# digital_clock_run4.net
KiCad netlist of a schematic drawn in EasyEDA
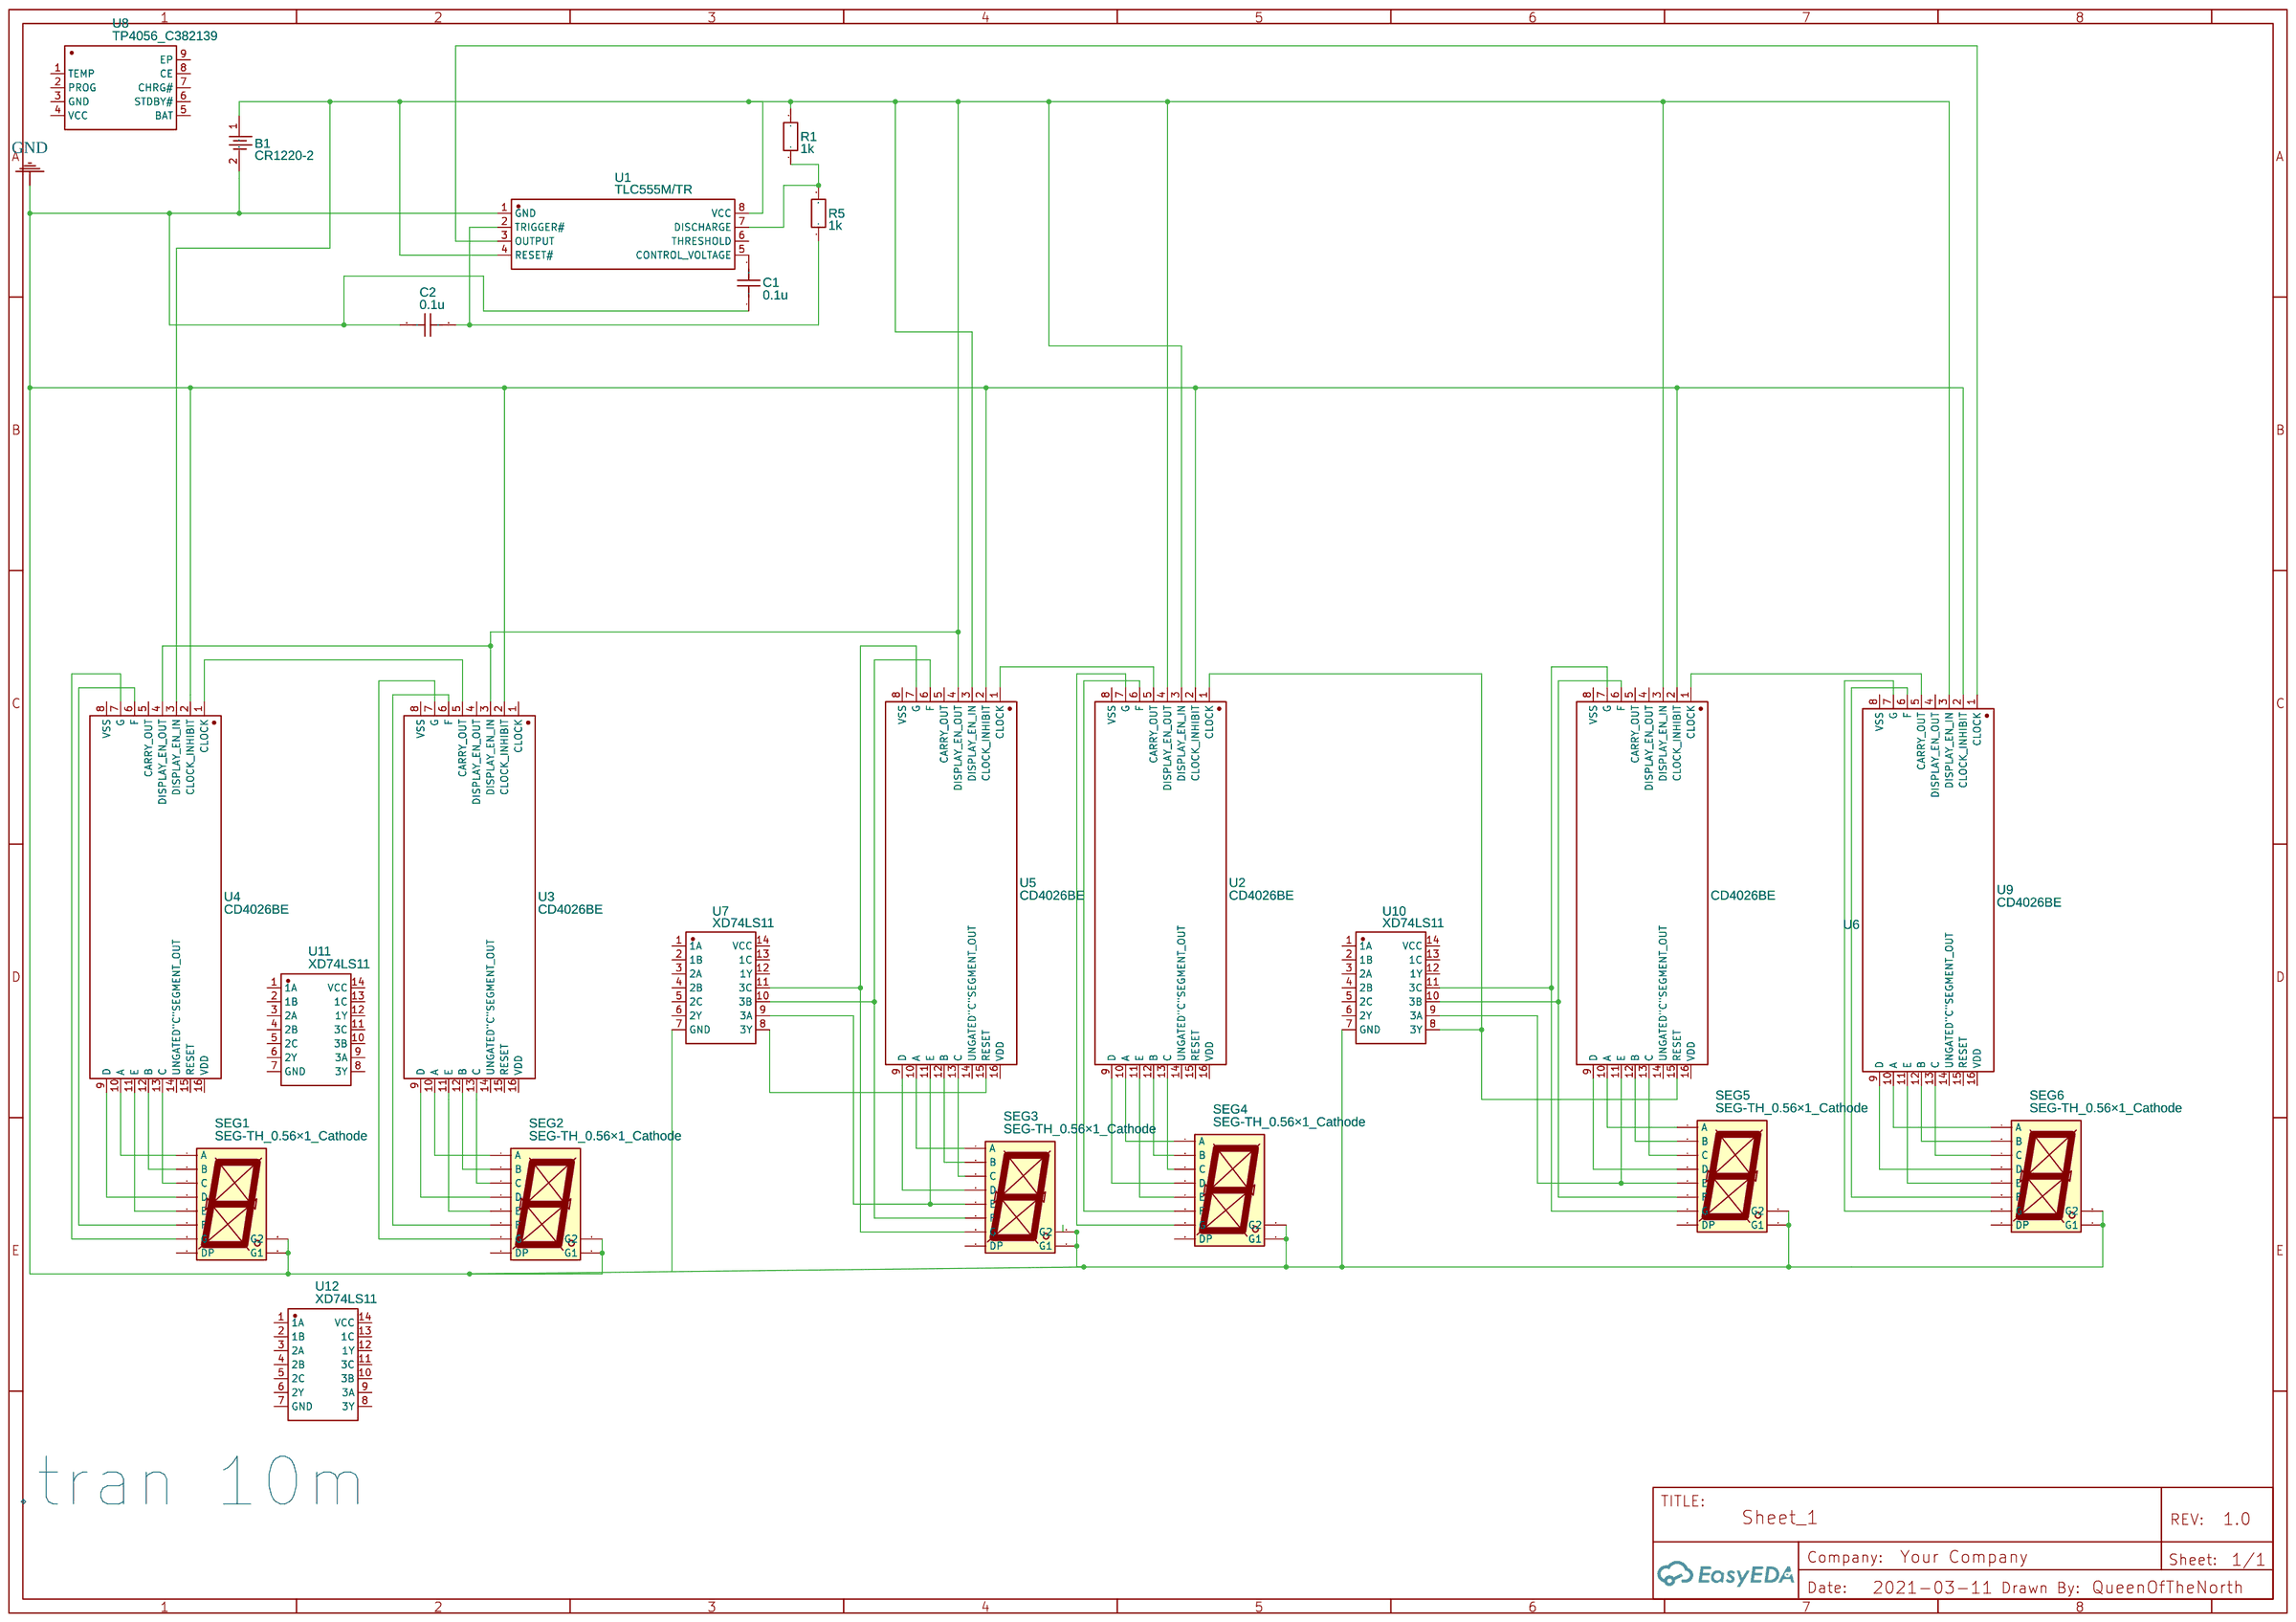
[diagram p0: schematic sheet]

(export (version "E")
  (design (tool "Eeschema 10.0.6"))
  (components
    (comp (ref "B1")
      (value "CR1220-2")
      (fields (field (name "BOM_Supplier Part") "C70381"))
      (libsource (lib "") (part "CR1220-2"))
    )
    (comp (ref "C1") (value "0.1u") (libsource (lib "") (part "C_0603_US")))
    (comp (ref "C2") (value "0.1u") (libsource (lib "") (part "C_0603_US_1")))
    (comp (ref "R1") (value "1k") (libsource (lib "") (part "R_0603_EU")))
    (comp (ref "R5") (value "1k") (libsource (lib "") (part "R_0603_EU")))
    (comp (ref "SEG1")
      (value "SEG-TH_0.56×1_Cathode")
      (fields (field (name "BOM_Supplier Part") "C8093"))
      (libsource (lib "") (part "SEG-TH_0.56×1_Cathode"))
    )
    (comp (ref "SEG2")
      (value "SEG-TH_0.56×1_Cathode")
      (fields (field (name "BOM_Supplier Part") "C8093"))
      (libsource (lib "") (part "SEG-TH_0.56×1_Cathode"))
    )
    (comp (ref "SEG3")
      (value "SEG-TH_0.56×1_Cathode")
      (fields (field (name "BOM_Supplier Part") "C8093"))
      (libsource (lib "") (part "SEG-TH_0.56×1_Cathode"))
    )
    (comp (ref "SEG4")
      (value "SEG-TH_0.56×1_Cathode")
      (fields (field (name "BOM_Supplier Part") "C8093"))
      (libsource (lib "") (part "SEG-TH_0.56×1_Cathode"))
    )
    (comp (ref "SEG5")
      (value "SEG-TH_0.56×1_Cathode")
      (fields (field (name "BOM_Supplier Part") "C8093"))
      (libsource (lib "") (part "SEG-TH_0.56×1_Cathode"))
    )
    (comp (ref "SEG6")
      (value "SEG-TH_0.56×1_Cathode")
      (fields (field (name "BOM_Supplier Part") "C8093"))
      (libsource (lib "") (part "SEG-TH_0.56×1_Cathode"))
    )
    (comp (ref "U1")
      (value "TLC555M/TR")
      (fields (field (name "BOM_Supplier Part") "C383061"))
      (libsource (lib "") (part "TLC555M/TR"))
    )
    (comp (ref "U2")
      (value "CD4026BE")
      (fields (field (name "BOM_Supplier Part") "C89909"))
      (libsource (lib "") (part "CD4026BE"))
    )
    (comp (ref "U3")
      (value "CD4026BE")
      (fields (field (name "BOM_Supplier Part") "C89909"))
      (libsource (lib "") (part "CD4026BE"))
    )
    (comp (ref "U4")
      (value "CD4026BE")
      (fields (field (name "BOM_Supplier Part") "C89909"))
      (libsource (lib "") (part "CD4026BE"))
    )
    (comp (ref "U5")
      (value "CD4026BE")
      (fields (field (name "BOM_Supplier Part") "C89909"))
      (libsource (lib "") (part "CD4026BE"))
    )
    (comp (ref "U6")
      (value "CD4026BE")
      (fields (field (name "BOM_Supplier Part") "C89909"))
      (libsource (lib "") (part "CD4026BE"))
    )
    (comp (ref "U7")
      (value "XD74LS11")
      (fields (field (name "BOM_Supplier Part") "C521167"))
      (libsource (lib "") (part "XD74LS11"))
    )
    (comp (ref "U8")
      (value "TP4056_C382139")
      (fields (field (name "BOM_Manufacturer Part") "TP4056") (field (name "BOM_Supplier Part") "C382139"))
      (libsource (lib "") (part "TP4056_C382139"))
    )
    (comp (ref "U9")
      (value "CD4026BE")
      (fields (field (name "BOM_Supplier Part") "C89909"))
      (libsource (lib "") (part "CD4026BE"))
    )
    (comp (ref "U10")
      (value "XD74LS11")
      (fields (field (name "BOM_Supplier Part") "C521167"))
      (libsource (lib "") (part "XD74LS11"))
    )
    (comp (ref "U11")
      (value "XD74LS11")
      (fields (field (name "BOM_Supplier Part") "C521167"))
      (libsource (lib "") (part "XD74LS11"))
    )
    (comp (ref "U12")
      (value "XD74LS11")
      (fields (field (name "BOM_Supplier Part") "C521167"))
      (libsource (lib "") (part "XD74LS11"))
    )
  )
  (nets
    (net (code "1") (name "GND") (class "Default")
      (node (ref "B1") (pin "2") (pinfunction "2_2") (pintype "input"))
      (node (ref "C1") (pin "1") (pinfunction "1_1") (pintype "unspecified"))
      (node (ref "C2") (pin "1") (pinfunction "1_1") (pintype "unspecified"))
      (node (ref "SEG1") (pin "3") (pinfunction "G1_3") (pintype "unspecified"))
      (node (ref "SEG1") (pin "8") (pinfunction "G2_8") (pintype "unspecified"))
      (node (ref "SEG2") (pin "3") (pinfunction "G1_3") (pintype "unspecified"))
      (node (ref "SEG2") (pin "8") (pinfunction "G2_8") (pintype "unspecified"))
      (node (ref "SEG3") (pin "3") (pinfunction "G1_3") (pintype "unspecified"))
      (node (ref "SEG3") (pin "8") (pinfunction "G2_8") (pintype "unspecified"))
      (node (ref "SEG4") (pin "3") (pinfunction "G1_3") (pintype "unspecified"))
      (node (ref "SEG4") (pin "8") (pinfunction "G2_8") (pintype "unspecified"))
      (node (ref "SEG5") (pin "3") (pinfunction "G1_3") (pintype "unspecified"))
      (node (ref "SEG5") (pin "8") (pinfunction "G2_8") (pintype "unspecified"))
      (node (ref "SEG6") (pin "3") (pinfunction "G1_3") (pintype "unspecified"))
      (node (ref "SEG6") (pin "8") (pinfunction "G2_8") (pintype "unspecified"))
      (node (ref "U1") (pin "1") (pinfunction "GND_1") (pintype "unspecified"))
      (node (ref "U10") (pin "7") (pinfunction "GND_7") (pintype "unspecified"))
      (node (ref "U2") (pin "2") (pinfunction "CLOCK_INHIBIT_2") (pintype "unspecified"))
      (node (ref "U3") (pin "2") (pinfunction "CLOCK_INHIBIT_2") (pintype "unspecified"))
      (node (ref "U4") (pin "2") (pinfunction "CLOCK_INHIBIT_2") (pintype "unspecified"))
      (node (ref "U5") (pin "2") (pinfunction "CLOCK_INHIBIT_2") (pintype "unspecified"))
      (node (ref "U6") (pin "2") (pinfunction "CLOCK_INHIBIT_2") (pintype "unspecified"))
      (node (ref "U9") (pin "2") (pinfunction "CLOCK_INHIBIT_2") (pintype "unspecified"))
    )
    (net (code "2") (name "Net-(SEG1-A)") (class "Default")
      (node (ref "SEG1") (pin "7") (pinfunction "A_7") (pintype "unspecified"))
      (node (ref "U4") (pin "10") (pinfunction "A_10") (pintype "unspecified"))
    )
    (net (code "3") (name "Net-(SEG1-B)") (class "Default")
      (node (ref "SEG1") (pin "6") (pinfunction "B_6") (pintype "unspecified"))
      (node (ref "U4") (pin "12") (pinfunction "B_12") (pintype "unspecified"))
    )
    (net (code "4") (name "Net-(SEG1-C)") (class "Default")
      (node (ref "SEG1") (pin "4") (pinfunction "C_4") (pintype "unspecified"))
      (node (ref "U4") (pin "13") (pinfunction "C_13") (pintype "unspecified"))
    )
    (net (code "5") (name "Net-(SEG1-D)") (class "Default")
      (node (ref "SEG1") (pin "2") (pinfunction "D_2") (pintype "unspecified"))
      (node (ref "U4") (pin "9") (pinfunction "D_9") (pintype "unspecified"))
    )
    (net (code "6") (name "Net-(SEG1-E)") (class "Default")
      (node (ref "SEG1") (pin "1") (pinfunction "E_1") (pintype "unspecified"))
      (node (ref "U4") (pin "11") (pinfunction "E_11") (pintype "unspecified"))
    )
    (net (code "7") (name "Net-(SEG1-F)") (class "Default")
      (node (ref "SEG1") (pin "9") (pinfunction "F_9") (pintype "unspecified"))
      (node (ref "U4") (pin "6") (pinfunction "F_6") (pintype "unspecified"))
    )
    (net (code "8") (name "Net-(SEG1-G)") (class "Default")
      (node (ref "SEG1") (pin "10") (pinfunction "G_10") (pintype "unspecified"))
      (node (ref "U4") (pin "7") (pinfunction "G_7") (pintype "unspecified"))
    )
    (net (code "9") (name "Net-(SEG2-A)") (class "Default")
      (node (ref "SEG2") (pin "7") (pinfunction "A_7") (pintype "unspecified"))
      (node (ref "U3") (pin "10") (pinfunction "A_10") (pintype "unspecified"))
    )
    (net (code "10") (name "Net-(SEG2-B)") (class "Default")
      (node (ref "SEG2") (pin "6") (pinfunction "B_6") (pintype "unspecified"))
      (node (ref "U3") (pin "12") (pinfunction "B_12") (pintype "unspecified"))
    )
    (net (code "11") (name "Net-(SEG2-C)") (class "Default")
      (node (ref "SEG2") (pin "4") (pinfunction "C_4") (pintype "unspecified"))
      (node (ref "U3") (pin "13") (pinfunction "C_13") (pintype "unspecified"))
    )
    (net (code "12") (name "Net-(SEG2-D)") (class "Default")
      (node (ref "SEG2") (pin "2") (pinfunction "D_2") (pintype "unspecified"))
      (node (ref "U3") (pin "9") (pinfunction "D_9") (pintype "unspecified"))
    )
    (net (code "13") (name "Net-(SEG2-E)") (class "Default")
      (node (ref "SEG2") (pin "1") (pinfunction "E_1") (pintype "unspecified"))
      (node (ref "U3") (pin "11") (pinfunction "E_11") (pintype "unspecified"))
    )
    (net (code "14") (name "Net-(SEG2-F)") (class "Default")
      (node (ref "SEG2") (pin "9") (pinfunction "F_9") (pintype "unspecified"))
      (node (ref "U3") (pin "6") (pinfunction "F_6") (pintype "unspecified"))
    )
    (net (code "15") (name "Net-(SEG2-G)") (class "Default")
      (node (ref "SEG2") (pin "10") (pinfunction "G_10") (pintype "unspecified"))
      (node (ref "U3") (pin "7") (pinfunction "G_7") (pintype "unspecified"))
    )
    (net (code "16") (name "Net-(SEG3-A)") (class "Default")
      (node (ref "SEG3") (pin "7") (pinfunction "A_7") (pintype "unspecified"))
      (node (ref "U5") (pin "10") (pinfunction "A_10") (pintype "unspecified"))
    )
    (net (code "17") (name "Net-(SEG3-B)") (class "Default")
      (node (ref "SEG3") (pin "6") (pinfunction "B_6") (pintype "unspecified"))
      (node (ref "U5") (pin "12") (pinfunction "B_12") (pintype "unspecified"))
    )
    (net (code "18") (name "Net-(SEG3-C)") (class "Default")
      (node (ref "SEG3") (pin "4") (pinfunction "C_4") (pintype "unspecified"))
      (node (ref "U5") (pin "13") (pinfunction "C_13") (pintype "unspecified"))
    )
    (net (code "19") (name "Net-(SEG3-D)") (class "Default")
      (node (ref "SEG3") (pin "2") (pinfunction "D_2") (pintype "unspecified"))
      (node (ref "U5") (pin "9") (pinfunction "D_9") (pintype "unspecified"))
    )
    (net (code "20") (name "Net-(SEG3-E)") (class "Default")
      (node (ref "SEG3") (pin "1") (pinfunction "E_1") (pintype "unspecified"))
      (node (ref "U5") (pin "11") (pinfunction "E_11") (pintype "unspecified"))
      (node (ref "U7") (pin "9") (pinfunction "3A_9") (pintype "unspecified"))
    )
    (net (code "21") (name "Net-(SEG3-F)") (class "Default")
      (node (ref "SEG3") (pin "9") (pinfunction "F_9") (pintype "unspecified"))
      (node (ref "U5") (pin "6") (pinfunction "F_6") (pintype "unspecified"))
      (node (ref "U7") (pin "10") (pinfunction "3B_10") (pintype "unspecified"))
    )
    (net (code "22") (name "Net-(SEG3-G)") (class "Default")
      (node (ref "SEG3") (pin "10") (pinfunction "G_10") (pintype "unspecified"))
      (node (ref "U5") (pin "7") (pinfunction "G_7") (pintype "unspecified"))
      (node (ref "U7") (pin "11") (pinfunction "3C_11") (pintype "unspecified"))
    )
    (net (code "23") (name "Net-(SEG4-A)") (class "Default")
      (node (ref "SEG4") (pin "7") (pinfunction "A_7") (pintype "unspecified"))
      (node (ref "U2") (pin "10") (pinfunction "A_10") (pintype "unspecified"))
    )
    (net (code "24") (name "Net-(SEG4-B)") (class "Default")
      (node (ref "SEG4") (pin "6") (pinfunction "B_6") (pintype "unspecified"))
      (node (ref "U2") (pin "12") (pinfunction "B_12") (pintype "unspecified"))
    )
    (net (code "25") (name "Net-(SEG4-C)") (class "Default")
      (node (ref "SEG4") (pin "4") (pinfunction "C_4") (pintype "unspecified"))
      (node (ref "U2") (pin "13") (pinfunction "C_13") (pintype "unspecified"))
    )
    (net (code "26") (name "Net-(SEG4-D)") (class "Default")
      (node (ref "SEG4") (pin "2") (pinfunction "D_2") (pintype "unspecified"))
      (node (ref "U2") (pin "9") (pinfunction "D_9") (pintype "unspecified"))
    )
    (net (code "27") (name "Net-(SEG4-E)") (class "Default")
      (node (ref "SEG4") (pin "1") (pinfunction "E_1") (pintype "unspecified"))
      (node (ref "U2") (pin "11") (pinfunction "E_11") (pintype "unspecified"))
    )
    (net (code "28") (name "Net-(SEG4-F)") (class "Default")
      (node (ref "SEG4") (pin "9") (pinfunction "F_9") (pintype "unspecified"))
      (node (ref "U2") (pin "6") (pinfunction "F_6") (pintype "unspecified"))
    )
    (net (code "29") (name "Net-(SEG4-G)") (class "Default")
      (node (ref "SEG4") (pin "10") (pinfunction "G_10") (pintype "unspecified"))
      (node (ref "U2") (pin "7") (pinfunction "G_7") (pintype "unspecified"))
    )
    (net (code "30") (name "Net-(SEG5-A)") (class "Default")
      (node (ref "SEG5") (pin "7") (pinfunction "A_7") (pintype "unspecified"))
      (node (ref "U6") (pin "10") (pinfunction "A_10") (pintype "unspecified"))
    )
    (net (code "31") (name "Net-(SEG5-B)") (class "Default")
      (node (ref "SEG5") (pin "6") (pinfunction "B_6") (pintype "unspecified"))
      (node (ref "U6") (pin "12") (pinfunction "B_12") (pintype "unspecified"))
    )
    (net (code "32") (name "Net-(SEG5-C)") (class "Default")
      (node (ref "SEG5") (pin "4") (pinfunction "C_4") (pintype "unspecified"))
      (node (ref "U6") (pin "13") (pinfunction "C_13") (pintype "unspecified"))
    )
    (net (code "33") (name "Net-(SEG5-D)") (class "Default")
      (node (ref "SEG5") (pin "2") (pinfunction "D_2") (pintype "unspecified"))
      (node (ref "U6") (pin "9") (pinfunction "D_9") (pintype "unspecified"))
    )
    (net (code "34") (name "Net-(SEG5-E)") (class "Default")
      (node (ref "SEG5") (pin "1") (pinfunction "E_1") (pintype "unspecified"))
      (node (ref "U10") (pin "9") (pinfunction "3A_9") (pintype "unspecified"))
      (node (ref "U6") (pin "11") (pinfunction "E_11") (pintype "unspecified"))
    )
    (net (code "35") (name "Net-(SEG5-F)") (class "Default")
      (node (ref "SEG5") (pin "9") (pinfunction "F_9") (pintype "unspecified"))
      (node (ref "U10") (pin "10") (pinfunction "3B_10") (pintype "unspecified"))
      (node (ref "U6") (pin "6") (pinfunction "F_6") (pintype "unspecified"))
    )
    (net (code "36") (name "Net-(SEG5-G)") (class "Default")
      (node (ref "SEG5") (pin "10") (pinfunction "G_10") (pintype "unspecified"))
      (node (ref "U10") (pin "11") (pinfunction "3C_11") (pintype "unspecified"))
      (node (ref "U6") (pin "7") (pinfunction "G_7") (pintype "unspecified"))
    )
    (net (code "37") (name "Net-(SEG6-A)") (class "Default")
      (node (ref "SEG6") (pin "7") (pinfunction "A_7") (pintype "unspecified"))
      (node (ref "U9") (pin "10") (pinfunction "A_10") (pintype "unspecified"))
    )
    (net (code "38") (name "Net-(SEG6-B)") (class "Default")
      (node (ref "SEG6") (pin "6") (pinfunction "B_6") (pintype "unspecified"))
      (node (ref "U9") (pin "12") (pinfunction "B_12") (pintype "unspecified"))
    )
    (net (code "39") (name "Net-(SEG6-C)") (class "Default")
      (node (ref "SEG6") (pin "4") (pinfunction "C_4") (pintype "unspecified"))
      (node (ref "U9") (pin "13") (pinfunction "C_13") (pintype "unspecified"))
    )
    (net (code "40") (name "Net-(SEG6-D)") (class "Default")
      (node (ref "SEG6") (pin "2") (pinfunction "D_2") (pintype "unspecified"))
      (node (ref "U9") (pin "9") (pinfunction "D_9") (pintype "unspecified"))
    )
    (net (code "41") (name "Net-(SEG6-E)") (class "Default")
      (node (ref "SEG6") (pin "1") (pinfunction "E_1") (pintype "unspecified"))
      (node (ref "U9") (pin "11") (pinfunction "E_11") (pintype "unspecified"))
    )
    (net (code "42") (name "Net-(SEG6-F)") (class "Default")
      (node (ref "SEG6") (pin "9") (pinfunction "F_9") (pintype "unspecified"))
      (node (ref "U9") (pin "6") (pinfunction "F_6") (pintype "unspecified"))
    )
    (net (code "43") (name "Net-(SEG6-G)") (class "Default")
      (node (ref "SEG6") (pin "10") (pinfunction "G_10") (pintype "unspecified"))
      (node (ref "U9") (pin "7") (pinfunction "G_7") (pintype "unspecified"))
    )
    (net (code "44") (name "Net-(U1-CONTROL_VOLTAGE)") (class "Default")
      (node (ref "C1") (pin "2") (pinfunction "2_2") (pintype "unspecified"))
      (node (ref "U1") (pin "5") (pinfunction "CONTROL_VOLTAGE_5") (pintype "unspecified"))
    )
    (net (code "45") (name "Net-(U1-DISCHARGE)") (class "Default")
      (node (ref "R1") (pin "1") (pinfunction "1_1") (pintype "unspecified"))
      (node (ref "R5") (pin "2") (pinfunction "2_2") (pintype "unspecified"))
      (node (ref "U1") (pin "7") (pinfunction "DISCHARGE_7") (pintype "unspecified"))
    )
    (net (code "46") (name "Net-(U1-OUTPUT)") (class "Default")
      (node (ref "U1") (pin "3") (pinfunction "OUTPUT_3") (pintype "unspecified"))
      (node (ref "U9") (pin "1") (pinfunction "CLOCK_1") (pintype "unspecified"))
    )
    (net (code "47") (name "Net-(U1-RESET#)") (class "Default")
      (node (ref "B1") (pin "1") (pinfunction "1_1") (pintype "input"))
      (node (ref "R1") (pin "2") (pinfunction "2_2") (pintype "unspecified"))
      (node (ref "U1") (pin "4") (pinfunction "RESET#_4") (pintype "unspecified"))
      (node (ref "U1") (pin "8") (pinfunction "VCC_8") (pintype "unspecified"))
      (node (ref "U2") (pin "3") (pinfunction "DISPLAY_EN_IN_3") (pintype "unspecified"))
      (node (ref "U2") (pin "4") (pinfunction "DISPLAY_EN_OUT_4") (pintype "unspecified"))
      (node (ref "U3") (pin "3") (pinfunction "DISPLAY_EN_IN_3") (pintype "unspecified"))
      (node (ref "U4") (pin "3") (pinfunction "DISPLAY_EN_IN_3") (pintype "unspecified"))
      (node (ref "U4") (pin "4") (pinfunction "DISPLAY_EN_OUT_4") (pintype "unspecified"))
      (node (ref "U5") (pin "3") (pinfunction "DISPLAY_EN_IN_3") (pintype "unspecified"))
      (node (ref "U5") (pin "4") (pinfunction "DISPLAY_EN_OUT_4") (pintype "unspecified"))
      (node (ref "U6") (pin "3") (pinfunction "DISPLAY_EN_IN_3") (pintype "unspecified"))
      (node (ref "U9") (pin "3") (pinfunction "DISPLAY_EN_IN_3") (pintype "unspecified"))
    )
    (net (code "48") (name "Net-(U1-TRIGGER#)") (class "Default")
      (node (ref "C2") (pin "2") (pinfunction "2_2") (pintype "unspecified"))
      (node (ref "R5") (pin "1") (pinfunction "1_1") (pintype "unspecified"))
      (node (ref "U1") (pin "2") (pinfunction "TRIGGER#_2") (pintype "unspecified"))
    )
    (net (code "49") (name "Net-(U2-CARRY_OUT)") (class "Default")
      (node (ref "U2") (pin "5") (pinfunction "CARRY_OUT_5") (pintype "unspecified"))
      (node (ref "U5") (pin "1") (pinfunction "CLOCK_1") (pintype "unspecified"))
    )
    (net (code "50") (name "Net-(U3-CARRY_OUT)") (class "Default")
      (node (ref "U3") (pin "5") (pinfunction "CARRY_OUT_5") (pintype "unspecified"))
      (node (ref "U4") (pin "1") (pinfunction "CLOCK_1") (pintype "unspecified"))
    )
    (net (code "51") (name "Net-(U5-RESET)") (class "Default")
      (node (ref "U5") (pin "15") (pinfunction "RESET_15") (pintype "unspecified"))
      (node (ref "U7") (pin "8") (pinfunction "3Y_8") (pintype "unspecified"))
    )
    (net (code "52") (name "Net-(U6-CLOCK)") (class "Default")
      (node (ref "U6") (pin "1") (pinfunction "CLOCK_1") (pintype "unspecified"))
      (node (ref "U9") (pin "5") (pinfunction "CARRY_OUT_5") (pintype "unspecified"))
    )
    (net (code "53") (name "Net-(U10-3Y)") (class "Default")
      (node (ref "U10") (pin "8") (pinfunction "3Y_8") (pintype "unspecified"))
      (node (ref "U2") (pin "1") (pinfunction "CLOCK_1") (pintype "unspecified"))
      (node (ref "U6") (pin "15") (pinfunction "RESET_15") (pintype "unspecified"))
    )
    (net (code "54") (name "unconnected-(SEG1-DP-Pad5)") (class "Default")
      (node (ref "SEG1") (pin "5") (pinfunction "DP_5") (pintype "unspecified"))
    )
    (net (code "55") (name "unconnected-(SEG2-DP-Pad5)") (class "Default")
      (node (ref "SEG2") (pin "5") (pinfunction "DP_5") (pintype "unspecified"))
    )
    (net (code "56") (name "unconnected-(SEG3-DP-Pad5)") (class "Default")
      (node (ref "SEG3") (pin "5") (pinfunction "DP_5") (pintype "unspecified"))
    )
    (net (code "57") (name "unconnected-(SEG4-DP-Pad5)") (class "Default")
      (node (ref "SEG4") (pin "5") (pinfunction "DP_5") (pintype "unspecified"))
    )
    (net (code "58") (name "unconnected-(SEG5-DP-Pad5)") (class "Default")
      (node (ref "SEG5") (pin "5") (pinfunction "DP_5") (pintype "unspecified"))
    )
    (net (code "59") (name "unconnected-(SEG6-DP-Pad5)") (class "Default")
      (node (ref "SEG6") (pin "5") (pinfunction "DP_5") (pintype "unspecified"))
    )
    (net (code "60") (name "unconnected-(U1-THRESHOLD-Pad6)") (class "Default")
      (node (ref "U1") (pin "6") (pinfunction "THRESHOLD_6") (pintype "unspecified"))
    )
    (net (code "61") (name "unconnected-(U2-RESET-Pad15)") (class "Default")
      (node (ref "U2") (pin "15") (pinfunction "RESET_15") (pintype "unspecified"))
    )
    (net (code "62") (name "unconnected-(U2-UNGATED\"C\"SEGMENT_OUT-Pad14)") (class "Default")
      (node (ref "U2") (pin "14") (pinfunction "UNGATED\"C\"SEGMENT_OUT_14") (pintype "unspecified"))
    )
    (net (code "63") (name "unconnected-(U2-VDD-Pad16)") (class "Default")
      (node (ref "U2") (pin "16") (pinfunction "VDD_16") (pintype "unspecified"))
    )
    (net (code "64") (name "unconnected-(U2-VSS-Pad8)") (class "Default")
      (node (ref "U2") (pin "8") (pinfunction "VSS_8") (pintype "unspecified"))
    )
    (net (code "65") (name "unconnected-(U3-CLOCK-Pad1)") (class "Default")
      (node (ref "U3") (pin "1") (pinfunction "CLOCK_1") (pintype "unspecified"))
    )
    (net (code "66") (name "unconnected-(U3-DISPLAY_EN_OUT-Pad4)") (class "Default")
      (node (ref "U3") (pin "4") (pinfunction "DISPLAY_EN_OUT_4") (pintype "unspecified"))
    )
    (net (code "67") (name "unconnected-(U3-RESET-Pad15)") (class "Default")
      (node (ref "U3") (pin "15") (pinfunction "RESET_15") (pintype "unspecified"))
    )
    (net (code "68") (name "unconnected-(U3-UNGATED\"C\"SEGMENT_OUT-Pad14)") (class "Default")
      (node (ref "U3") (pin "14") (pinfunction "UNGATED\"C\"SEGMENT_OUT_14") (pintype "unspecified"))
    )
    (net (code "69") (name "unconnected-(U3-VDD-Pad16)") (class "Default")
      (node (ref "U3") (pin "16") (pinfunction "VDD_16") (pintype "unspecified"))
    )
    (net (code "70") (name "unconnected-(U3-VSS-Pad8)") (class "Default")
      (node (ref "U3") (pin "8") (pinfunction "VSS_8") (pintype "unspecified"))
    )
    (net (code "71") (name "unconnected-(U4-CARRY_OUT-Pad5)") (class "Default")
      (node (ref "U4") (pin "5") (pinfunction "CARRY_OUT_5") (pintype "unspecified"))
    )
    (net (code "72") (name "unconnected-(U4-RESET-Pad15)") (class "Default")
      (node (ref "U4") (pin "15") (pinfunction "RESET_15") (pintype "unspecified"))
    )
    (net (code "73") (name "unconnected-(U4-UNGATED\"C\"SEGMENT_OUT-Pad14)") (class "Default")
      (node (ref "U4") (pin "14") (pinfunction "UNGATED\"C\"SEGMENT_OUT_14") (pintype "unspecified"))
    )
    (net (code "74") (name "unconnected-(U4-VDD-Pad16)") (class "Default")
      (node (ref "U4") (pin "16") (pinfunction "VDD_16") (pintype "unspecified"))
    )
    (net (code "75") (name "unconnected-(U4-VSS-Pad8)") (class "Default")
      (node (ref "U4") (pin "8") (pinfunction "VSS_8") (pintype "unspecified"))
    )
    (net (code "76") (name "unconnected-(U5-CARRY_OUT-Pad5)") (class "Default")
      (node (ref "U5") (pin "5") (pinfunction "CARRY_OUT_5") (pintype "unspecified"))
    )
    (net (code "77") (name "unconnected-(U5-UNGATED\"C\"SEGMENT_OUT-Pad14)") (class "Default")
      (node (ref "U5") (pin "14") (pinfunction "UNGATED\"C\"SEGMENT_OUT_14") (pintype "unspecified"))
    )
    (net (code "78") (name "unconnected-(U5-VDD-Pad16)") (class "Default")
      (node (ref "U5") (pin "16") (pinfunction "VDD_16") (pintype "unspecified"))
    )
    (net (code "79") (name "unconnected-(U5-VSS-Pad8)") (class "Default")
      (node (ref "U5") (pin "8") (pinfunction "VSS_8") (pintype "unspecified"))
    )
    (net (code "80") (name "unconnected-(U6-CARRY_OUT-Pad5)") (class "Default")
      (node (ref "U6") (pin "5") (pinfunction "CARRY_OUT_5") (pintype "unspecified"))
    )
    (net (code "81") (name "unconnected-(U6-DISPLAY_EN_OUT-Pad4)") (class "Default")
      (node (ref "U6") (pin "4") (pinfunction "DISPLAY_EN_OUT_4") (pintype "unspecified"))
    )
    (net (code "82") (name "unconnected-(U6-UNGATED\"C\"SEGMENT_OUT-Pad14)") (class "Default")
      (node (ref "U6") (pin "14") (pinfunction "UNGATED\"C\"SEGMENT_OUT_14") (pintype "unspecified"))
    )
    (net (code "83") (name "unconnected-(U6-VDD-Pad16)") (class "Default")
      (node (ref "U6") (pin "16") (pinfunction "VDD_16") (pintype "unspecified"))
    )
    (net (code "84") (name "unconnected-(U6-VSS-Pad8)") (class "Default")
      (node (ref "U6") (pin "8") (pinfunction "VSS_8") (pintype "unspecified"))
    )
    (net (code "85") (name "unconnected-(U7-1A-Pad1)") (class "Default")
      (node (ref "U7") (pin "1") (pinfunction "1A_1") (pintype "unspecified"))
    )
    (net (code "86") (name "unconnected-(U7-1B-Pad2)") (class "Default")
      (node (ref "U7") (pin "2") (pinfunction "1B_2") (pintype "unspecified"))
    )
    (net (code "87") (name "unconnected-(U7-1C-Pad13)") (class "Default")
      (node (ref "U7") (pin "13") (pinfunction "1C_13") (pintype "unspecified"))
    )
    (net (code "88") (name "unconnected-(U7-1Y-Pad12)") (class "Default")
      (node (ref "U7") (pin "12") (pinfunction "1Y_12") (pintype "unspecified"))
    )
    (net (code "89") (name "unconnected-(U7-2A-Pad3)") (class "Default")
      (node (ref "U7") (pin "3") (pinfunction "2A_3") (pintype "unspecified"))
    )
    (net (code "90") (name "unconnected-(U7-2B-Pad4)") (class "Default")
      (node (ref "U7") (pin "4") (pinfunction "2B_4") (pintype "unspecified"))
    )
    (net (code "91") (name "unconnected-(U7-2C-Pad5)") (class "Default")
      (node (ref "U7") (pin "5") (pinfunction "2C_5") (pintype "unspecified"))
    )
    (net (code "92") (name "unconnected-(U7-2Y-Pad6)") (class "Default")
      (node (ref "U7") (pin "6") (pinfunction "2Y_6") (pintype "unspecified"))
    )
    (net (code "93") (name "unconnected-(U7-GND-Pad7)") (class "Default")
      (node (ref "U7") (pin "7") (pinfunction "GND_7") (pintype "unspecified"))
    )
    (net (code "94") (name "unconnected-(U7-VCC-Pad14)") (class "Default")
      (node (ref "U7") (pin "14") (pinfunction "VCC_14") (pintype "unspecified"))
    )
    (net (code "95") (name "unconnected-(U8-BAT-Pad5)") (class "Default")
      (node (ref "U8") (pin "5") (pinfunction "BAT_5") (pintype "unspecified"))
    )
    (net (code "96") (name "unconnected-(U8-CE-Pad8)") (class "Default")
      (node (ref "U8") (pin "8") (pinfunction "CE_8") (pintype "unspecified"))
    )
    (net (code "97") (name "unconnected-(U8-CHRG#-Pad7)") (class "Default")
      (node (ref "U8") (pin "7") (pinfunction "CHRG#_7") (pintype "unspecified"))
    )
    (net (code "98") (name "unconnected-(U8-EP-Pad9)") (class "Default")
      (node (ref "U8") (pin "9") (pinfunction "EP_9") (pintype "unspecified"))
    )
    (net (code "99") (name "unconnected-(U8-GND-Pad3)") (class "Default")
      (node (ref "U8") (pin "3") (pinfunction "GND_3") (pintype "unspecified"))
    )
    (net (code "100") (name "unconnected-(U8-PROG-Pad2)") (class "Default")
      (node (ref "U8") (pin "2") (pinfunction "PROG_2") (pintype "unspecified"))
    )
    (net (code "101") (name "unconnected-(U8-STDBY#-Pad6)") (class "Default")
      (node (ref "U8") (pin "6") (pinfunction "STDBY#_6") (pintype "unspecified"))
    )
    (net (code "102") (name "unconnected-(U8-TEMP-Pad1)") (class "Default")
      (node (ref "U8") (pin "1") (pinfunction "TEMP_1") (pintype "unspecified"))
    )
    (net (code "103") (name "unconnected-(U8-VCC-Pad4)") (class "Default")
      (node (ref "U8") (pin "4") (pinfunction "VCC_4") (pintype "unspecified"))
    )
    (net (code "104") (name "unconnected-(U9-DISPLAY_EN_OUT-Pad4)") (class "Default")
      (node (ref "U9") (pin "4") (pinfunction "DISPLAY_EN_OUT_4") (pintype "unspecified"))
    )
    (net (code "105") (name "unconnected-(U9-RESET-Pad15)") (class "Default")
      (node (ref "U9") (pin "15") (pinfunction "RESET_15") (pintype "unspecified"))
    )
    (net (code "106") (name "unconnected-(U9-UNGATED\"C\"SEGMENT_OUT-Pad14)") (class "Default")
      (node (ref "U9") (pin "14") (pinfunction "UNGATED\"C\"SEGMENT_OUT_14") (pintype "unspecified"))
    )
    (net (code "107") (name "unconnected-(U9-VDD-Pad16)") (class "Default")
      (node (ref "U9") (pin "16") (pinfunction "VDD_16") (pintype "unspecified"))
    )
    (net (code "108") (name "unconnected-(U9-VSS-Pad8)") (class "Default")
      (node (ref "U9") (pin "8") (pinfunction "VSS_8") (pintype "unspecified"))
    )
    (net (code "109") (name "unconnected-(U10-1A-Pad1)") (class "Default")
      (node (ref "U10") (pin "1") (pinfunction "1A_1") (pintype "unspecified"))
    )
    (net (code "110") (name "unconnected-(U10-1B-Pad2)") (class "Default")
      (node (ref "U10") (pin "2") (pinfunction "1B_2") (pintype "unspecified"))
    )
    (net (code "111") (name "unconnected-(U10-1C-Pad13)") (class "Default")
      (node (ref "U10") (pin "13") (pinfunction "1C_13") (pintype "unspecified"))
    )
    (net (code "112") (name "unconnected-(U10-1Y-Pad12)") (class "Default")
      (node (ref "U10") (pin "12") (pinfunction "1Y_12") (pintype "unspecified"))
    )
    (net (code "113") (name "unconnected-(U10-2A-Pad3)") (class "Default")
      (node (ref "U10") (pin "3") (pinfunction "2A_3") (pintype "unspecified"))
    )
    (net (code "114") (name "unconnected-(U10-2B-Pad4)") (class "Default")
      (node (ref "U10") (pin "4") (pinfunction "2B_4") (pintype "unspecified"))
    )
    (net (code "115") (name "unconnected-(U10-2C-Pad5)") (class "Default")
      (node (ref "U10") (pin "5") (pinfunction "2C_5") (pintype "unspecified"))
    )
    (net (code "116") (name "unconnected-(U10-2Y-Pad6)") (class "Default")
      (node (ref "U10") (pin "6") (pinfunction "2Y_6") (pintype "unspecified"))
    )
    (net (code "117") (name "unconnected-(U10-VCC-Pad14)") (class "Default")
      (node (ref "U10") (pin "14") (pinfunction "VCC_14") (pintype "unspecified"))
    )
    (net (code "118") (name "unconnected-(U11-1A-Pad1)") (class "Default")
      (node (ref "U11") (pin "1") (pinfunction "1A_1") (pintype "unspecified"))
    )
    (net (code "119") (name "unconnected-(U11-1B-Pad2)") (class "Default")
      (node (ref "U11") (pin "2") (pinfunction "1B_2") (pintype "unspecified"))
    )
    (net (code "120") (name "unconnected-(U11-1C-Pad13)") (class "Default")
      (node (ref "U11") (pin "13") (pinfunction "1C_13") (pintype "unspecified"))
    )
    (net (code "121") (name "unconnected-(U11-1Y-Pad12)") (class "Default")
      (node (ref "U11") (pin "12") (pinfunction "1Y_12") (pintype "unspecified"))
    )
    (net (code "122") (name "unconnected-(U11-2A-Pad3)") (class "Default")
      (node (ref "U11") (pin "3") (pinfunction "2A_3") (pintype "unspecified"))
    )
    (net (code "123") (name "unconnected-(U11-2B-Pad4)") (class "Default")
      (node (ref "U11") (pin "4") (pinfunction "2B_4") (pintype "unspecified"))
    )
    (net (code "124") (name "unconnected-(U11-2C-Pad5)") (class "Default")
      (node (ref "U11") (pin "5") (pinfunction "2C_5") (pintype "unspecified"))
    )
    (net (code "125") (name "unconnected-(U11-2Y-Pad6)") (class "Default")
      (node (ref "U11") (pin "6") (pinfunction "2Y_6") (pintype "unspecified"))
    )
    (net (code "126") (name "unconnected-(U11-3A-Pad9)") (class "Default")
      (node (ref "U11") (pin "9") (pinfunction "3A_9") (pintype "unspecified"))
    )
    (net (code "127") (name "unconnected-(U11-3B-Pad10)") (class "Default")
      (node (ref "U11") (pin "10") (pinfunction "3B_10") (pintype "unspecified"))
    )
    (net (code "128") (name "unconnected-(U11-3C-Pad11)") (class "Default")
      (node (ref "U11") (pin "11") (pinfunction "3C_11") (pintype "unspecified"))
    )
    (net (code "129") (name "unconnected-(U11-3Y-Pad8)") (class "Default")
      (node (ref "U11") (pin "8") (pinfunction "3Y_8") (pintype "unspecified"))
    )
    (net (code "130") (name "unconnected-(U11-GND-Pad7)") (class "Default")
      (node (ref "U11") (pin "7") (pinfunction "GND_7") (pintype "unspecified"))
    )
    (net (code "131") (name "unconnected-(U11-VCC-Pad14)") (class "Default")
      (node (ref "U11") (pin "14") (pinfunction "VCC_14") (pintype "unspecified"))
    )
    (net (code "132") (name "unconnected-(U12-1A-Pad1)") (class "Default")
      (node (ref "U12") (pin "1") (pinfunction "1A_1") (pintype "unspecified"))
    )
    (net (code "133") (name "unconnected-(U12-1B-Pad2)") (class "Default")
      (node (ref "U12") (pin "2") (pinfunction "1B_2") (pintype "unspecified"))
    )
    (net (code "134") (name "unconnected-(U12-1C-Pad13)") (class "Default")
      (node (ref "U12") (pin "13") (pinfunction "1C_13") (pintype "unspecified"))
    )
    (net (code "135") (name "unconnected-(U12-1Y-Pad12)") (class "Default")
      (node (ref "U12") (pin "12") (pinfunction "1Y_12") (pintype "unspecified"))
    )
    (net (code "136") (name "unconnected-(U12-2A-Pad3)") (class "Default")
      (node (ref "U12") (pin "3") (pinfunction "2A_3") (pintype "unspecified"))
    )
    (net (code "137") (name "unconnected-(U12-2B-Pad4)") (class "Default")
      (node (ref "U12") (pin "4") (pinfunction "2B_4") (pintype "unspecified"))
    )
    (net (code "138") (name "unconnected-(U12-2C-Pad5)") (class "Default")
      (node (ref "U12") (pin "5") (pinfunction "2C_5") (pintype "unspecified"))
    )
    (net (code "139") (name "unconnected-(U12-2Y-Pad6)") (class "Default")
      (node (ref "U12") (pin "6") (pinfunction "2Y_6") (pintype "unspecified"))
    )
    (net (code "140") (name "unconnected-(U12-3A-Pad9)") (class "Default")
      (node (ref "U12") (pin "9") (pinfunction "3A_9") (pintype "unspecified"))
    )
    (net (code "141") (name "unconnected-(U12-3B-Pad10)") (class "Default")
      (node (ref "U12") (pin "10") (pinfunction "3B_10") (pintype "unspecified"))
    )
    (net (code "142") (name "unconnected-(U12-3C-Pad11)") (class "Default")
      (node (ref "U12") (pin "11") (pinfunction "3C_11") (pintype "unspecified"))
    )
    (net (code "143") (name "unconnected-(U12-3Y-Pad8)") (class "Default")
      (node (ref "U12") (pin "8") (pinfunction "3Y_8") (pintype "unspecified"))
    )
    (net (code "144") (name "unconnected-(U12-GND-Pad7)") (class "Default")
      (node (ref "U12") (pin "7") (pinfunction "GND_7") (pintype "unspecified"))
    )
    (net (code "145") (name "unconnected-(U12-VCC-Pad14)") (class "Default")
      (node (ref "U12") (pin "14") (pinfunction "VCC_14") (pintype "unspecified"))
    )
  )
)
